# SH10_-_RS-485.net
KiCad netlist of a schematic drawn in Altium Designer
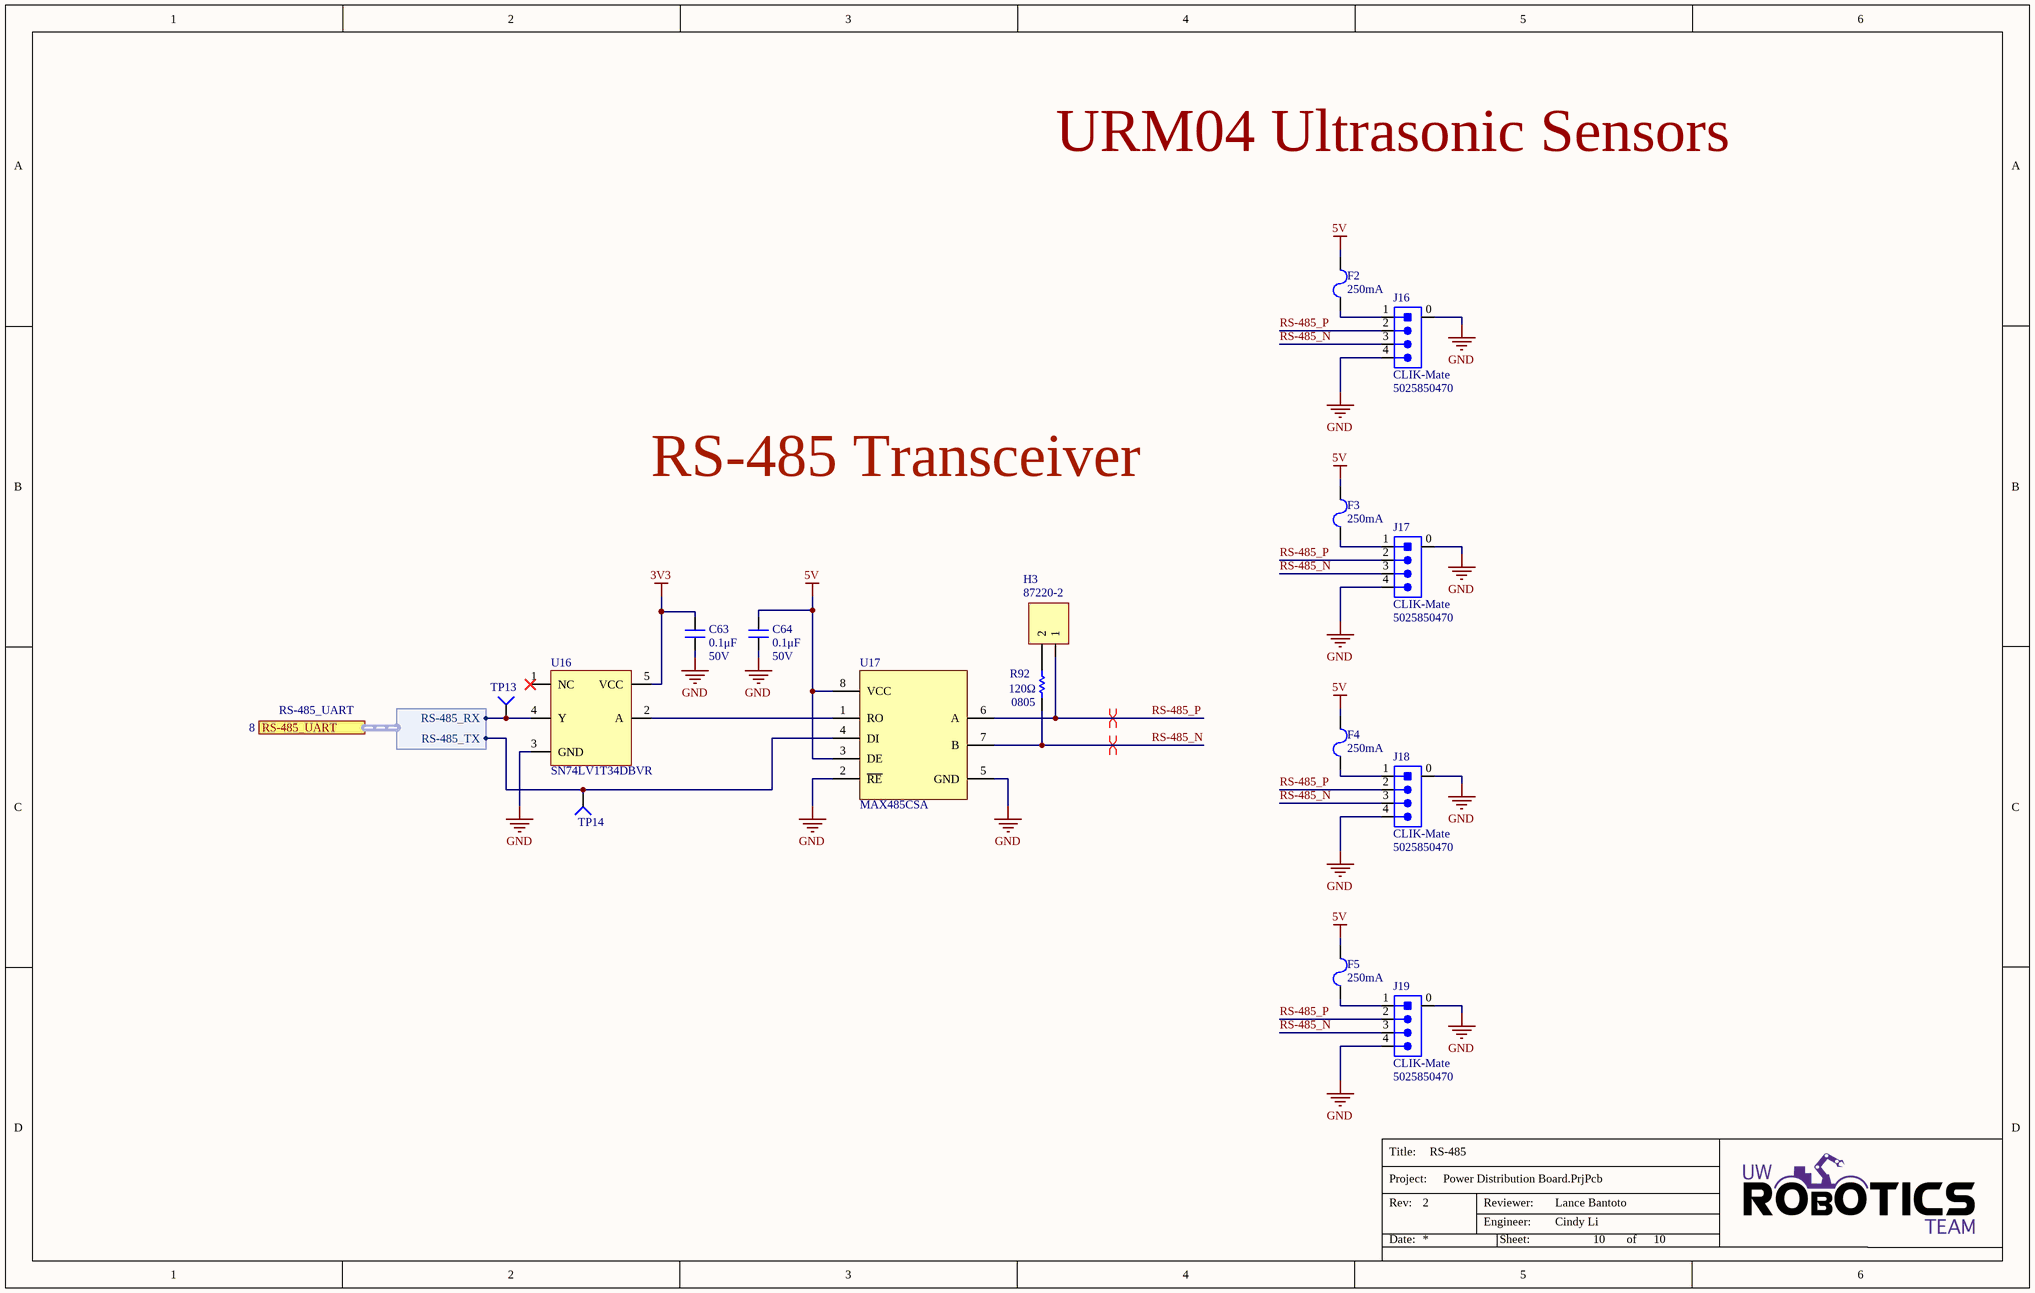
[diagram p0: SH10 - RS-485.SchDoc]

(export (version "E")
  (design (tool "Eeschema 10.0.6"))
  (components
    (comp (ref "C63")
      (value "0.1μF")
      (footprint "CAP2012")
      (description "CAP CER 0.1UF 50V X7R 0805")
      (fields
        (field (name "VOLTAGE RATING") "50V")
        (field (name "TOLERANCE") "10%")
        (field (name "LCSC PART #") "C49678")
      )
      (libsource (lib "UWRT_Schematic_Library_2020") (part "CAP_0.1uF_50V_0805"))
    )
    (comp (ref "C64")
      (value "0.1μF")
      (footprint "CAP2012")
      (description "CAP CER 0.1UF 50V X7R 0805")
      (fields
        (field (name "VOLTAGE RATING") "50V")
        (field (name "TOLERANCE") "10%")
        (field (name "LCSC PART #") "C49678")
      )
      (libsource (lib "UWRT_Schematic_Library_2020") (part "CAP_0.1uF_50V_0805"))
    )
    (comp (ref "F2")
      (value "FUSE_250mA_1206")
      (footprint "FUSE_1206")
      (description "FUSE BOARD MNT 250MA 125VAC/VDC")
      (fields (field (name "CURRENT RATING") "250mA"))
      (libsource (lib "UWRT_Schematic_Library_2020") (part "FUSE_250mA_1206"))
    )
    (comp (ref "F3")
      (value "FUSE_250mA_1206")
      (footprint "FUSE_1206")
      (description "FUSE BOARD MNT 250MA 125VAC/VDC")
      (fields (field (name "CURRENT RATING") "250mA"))
      (libsource (lib "UWRT_Schematic_Library_2020") (part "FUSE_250mA_1206"))
    )
    (comp (ref "F4")
      (value "FUSE_250mA_1206")
      (footprint "FUSE_1206")
      (description "FUSE BOARD MNT 250MA 125VAC/VDC")
      (fields (field (name "CURRENT RATING") "250mA"))
      (libsource (lib "UWRT_Schematic_Library_2020") (part "FUSE_250mA_1206"))
    )
    (comp (ref "F5")
      (value "FUSE_250mA_1206")
      (footprint "FUSE_1206")
      (description "FUSE BOARD MNT 250MA 125VAC/VDC")
      (fields (field (name "CURRENT RATING") "250mA"))
      (libsource (lib "UWRT_Schematic_Library_2020") (part "FUSE_250mA_1206"))
    )
    (comp (ref "H3")
      (value "JUMPER_2")
      (footprint "HDR1X2")
      (description "HEADER 2X1")
      (fields (field (name "MANUFACTURER PART NUMBER 1") "87220-2"))
      (libsource (lib "UWRT_Schematic_Library_2020") (part "JUMPER_2"))
    )
    (comp (ref "J16")
      (value "CON_4M_SM_RA")
      (footprint "MOLEX-5025850470")
      (description "CONN HEADER SMD RIGHT ANGLE 1.5 MM PITCH")
      (fields
        (field (name "MANUFACTURER") "Molex")
        (field (name "FAMILY") "CLIK-Mate")
        (field (name "MANUFACTOR NUMBER") "5025850470")
      )
      (libsource (lib "UWRT_Schematic_Library_2020") (part "CON_4M_SM_RA"))
    )
    (comp (ref "J17")
      (value "CON_4M_SM_RA")
      (footprint "MOLEX-5025850470")
      (description "CONN HEADER SMD RIGHT ANGLE 1.5 MM PITCH")
      (fields
        (field (name "MANUFACTURER") "Molex")
        (field (name "FAMILY") "CLIK-Mate")
        (field (name "MANUFACTOR NUMBER") "5025850470")
      )
      (libsource (lib "UWRT_Schematic_Library_2020") (part "CON_4M_SM_RA"))
    )
    (comp (ref "J18")
      (value "CON_4M_SM_RA")
      (footprint "MOLEX-5025850470")
      (description "CONN HEADER SMD RIGHT ANGLE 1.5 MM PITCH")
      (fields
        (field (name "MANUFACTURER") "Molex")
        (field (name "FAMILY") "CLIK-Mate")
        (field (name "MANUFACTOR NUMBER") "5025850470")
      )
      (libsource (lib "UWRT_Schematic_Library_2020") (part "CON_4M_SM_RA"))
    )
    (comp (ref "J19")
      (value "CON_4M_SM_RA")
      (footprint "MOLEX-5025850470")
      (description "CONN HEADER SMD RIGHT ANGLE 1.5 MM PITCH")
      (fields
        (field (name "MANUFACTURER") "Molex")
        (field (name "FAMILY") "CLIK-Mate")
        (field (name "MANUFACTOR NUMBER") "5025850470")
      )
      (libsource (lib "UWRT_Schematic_Library_2020") (part "CON_4M_SM_RA"))
    )
    (comp (ref "R92")
      (value "RES_120Ω_0805_1%")
      (footprint "RESC0805")
      (description "RES 120 OHM 1% 1/8W 0805")
      (fields
        (field (name "RESISTANCE") "120Ω")
        (field (name "LCSC PART #") "C17437")
        (field (name "PACKAGE/FOOTPRINT") "0805")
      )
      (libsource (lib "UWRT_Schematic_Library_2020") (part "RES_120Ω_0805_1%"))
    )
    (comp (ref "TP13")
      (value "TESTPOINT_1MM_CIRCLE")
      (footprint "TESTPOINT_CIRCLE_1MM")
      (description "TESTPOINT 1MM CIRCLE")
      (libsource (lib "UWRT_Schematic_Library_2020") (part "TESTPOINT_1MM_CIRCLE"))
    )
    (comp (ref "TP14")
      (value "TESTPOINT_1MM_CIRCLE")
      (footprint "TESTPOINT_CIRCLE_1MM")
      (description "TESTPOINT 1MM CIRCLE")
      (libsource (lib "UWRT_Schematic_Library_2020") (part "TESTPOINT_1MM_CIRCLE"))
    )
    (comp (ref "U16")
      (value "SN74LV1T34")
      (footprint "SN74LV1T34DBVR")
      (description "IC BUF NON-INVERT 5.5V SOT23-5")
      (fields
        (field (name "MANUFACTURER PART NUMBER 1") "SN74LV1T34DBVR")
        (field (name "LCSC PART #") "C100024")
      )
      (libsource (lib "UWRT_Schematic_Library_2020") (part "SN74LV1T34"))
    )
    (comp (ref "U17")
      (value "MAX485CSA")
      (footprint "SOIC127P600X175-8N")
      (description "IC TRANSCEIVER HALF 1/1 8SOIC RS422, RS485")
      (fields (field (name "LCSC PART #") "C9945"))
      (libsource (lib "UWRT_Schematic_Library_2020") (part "MAX485CSA"))
    )
  )
  (nets
    (net (code "2") (name "/RS-485_N") (class "Default")
      (node (ref "J16") (pin "3") (pinfunction "3_3") (pintype "passive"))
      (node (ref "J17") (pin "3") (pinfunction "3_3") (pintype "passive"))
      (node (ref "J18") (pin "3") (pinfunction "3_3") (pintype "passive"))
      (node (ref "J19") (pin "3") (pinfunction "3_3") (pintype "passive"))
      (node (ref "R92") (pin "1") (pinfunction "1_1") (pintype "passive"))
      (node (ref "U17") (pin "7") (pinfunction "B_7") (pintype "passive"))
    )
    (net (code "3") (name "/RS-485_P") (class "Default")
      (node (ref "H3") (pin "1") (pinfunction "1_1") (pintype "passive"))
      (node (ref "J16") (pin "2") (pinfunction "2_2") (pintype "passive"))
      (node (ref "J17") (pin "2") (pinfunction "2_2") (pintype "passive"))
      (node (ref "J18") (pin "2") (pinfunction "2_2") (pintype "passive"))
      (node (ref "J19") (pin "2") (pinfunction "2_2") (pintype "passive"))
      (node (ref "U17") (pin "6") (pinfunction "A_6") (pintype "passive"))
    )
    (net (code "5") (name "3V3") (class "Default")
      (node (ref "C63") (pin "1") (pinfunction "1_1") (pintype "passive"))
      (node (ref "U16") (pin "5") (pinfunction "VCC_5") (pintype "passive"))
    )
    (net (code "6") (name "5V") (class "Default")
      (node (ref "C64") (pin "1") (pinfunction "1_1") (pintype "passive"))
      (node (ref "F2") (pin "2") (pinfunction "2_2") (pintype "passive"))
      (node (ref "F3") (pin "2") (pinfunction "2_2") (pintype "passive"))
      (node (ref "F4") (pin "2") (pinfunction "2_2") (pintype "passive"))
      (node (ref "F5") (pin "2") (pinfunction "2_2") (pintype "passive"))
      (node (ref "U17") (pin "3") (pinfunction "DE_3") (pintype "passive"))
      (node (ref "U17") (pin "8") (pinfunction "VCC_8") (pintype "power_in"))
    )
    (net (code "7") (name "GND") (class "Default")
      (node (ref "C63") (pin "2") (pinfunction "2_2") (pintype "passive"))
      (node (ref "C64") (pin "2") (pinfunction "2_2") (pintype "passive"))
      (node (ref "J16") (pin "0") (pinfunction "0_0") (pintype "passive"))
      (node (ref "J16") (pin "4") (pinfunction "4_4") (pintype "passive"))
      (node (ref "J17") (pin "0") (pinfunction "0_0") (pintype "passive"))
      (node (ref "J17") (pin "4") (pinfunction "4_4") (pintype "passive"))
      (node (ref "J18") (pin "0") (pinfunction "0_0") (pintype "passive"))
      (node (ref "J18") (pin "4") (pinfunction "4_4") (pintype "passive"))
      (node (ref "J19") (pin "0") (pinfunction "0_0") (pintype "passive"))
      (node (ref "J19") (pin "4") (pinfunction "4_4") (pintype "passive"))
      (node (ref "U16") (pin "3") (pinfunction "GND_3") (pintype "passive"))
      (node (ref "U17") (pin "2") (pinfunction "~{RE}_2") (pintype "passive"))
      (node (ref "U17") (pin "5") (pinfunction "GND_5") (pintype "power_in"))
    )
    (net (code "8") (name "Net-(F2-Pad1)") (class "Default")
      (node (ref "F2") (pin "1") (pinfunction "1_1") (pintype "passive"))
      (node (ref "J16") (pin "1") (pinfunction "1_1") (pintype "passive"))
    )
    (net (code "9") (name "Net-(F3-Pad1)") (class "Default")
      (node (ref "F3") (pin "1") (pinfunction "1_1") (pintype "passive"))
      (node (ref "J17") (pin "1") (pinfunction "1_1") (pintype "passive"))
    )
    (net (code "10") (name "Net-(F4-Pad1)") (class "Default")
      (node (ref "F4") (pin "1") (pinfunction "1_1") (pintype "passive"))
      (node (ref "J18") (pin "1") (pinfunction "1_1") (pintype "passive"))
    )
    (net (code "11") (name "Net-(F5-Pad1)") (class "Default")
      (node (ref "F5") (pin "1") (pinfunction "1_1") (pintype "passive"))
      (node (ref "J19") (pin "1") (pinfunction "1_1") (pintype "passive"))
    )
    (net (code "12") (name "Net-(H3-Pad2)") (class "Default")
      (node (ref "H3") (pin "2") (pinfunction "2_2") (pintype "passive"))
      (node (ref "R92") (pin "2") (pinfunction "2_2") (pintype "passive"))
    )
    (net (code "13") (name "Net-(TP13-=value)") (class "Default")
      (node (ref "TP13") (pin "1") (pinfunction "=value_1") (pintype "passive"))
      (node (ref "U16") (pin "4") (pinfunction "Y_4") (pintype "passive"))
    )
    (net (code "14") (name "Net-(TP14-=value)") (class "Default")
      (node (ref "TP14") (pin "1") (pinfunction "=value_1") (pintype "passive"))
      (node (ref "U17") (pin "4") (pinfunction "DI_4") (pintype "passive"))
    )
    (net (code "15") (name "Net-(U16-A)") (class "Default")
      (node (ref "U16") (pin "2") (pinfunction "A_2") (pintype "passive"))
      (node (ref "U17") (pin "1") (pinfunction "RO_1") (pintype "passive"))
    )
    (net (code "16") (name "unconnected-(U16-NC-Pad1)") (class "Default")
      (node (ref "U16") (pin "1") (pinfunction "NC_1") (pintype "passive+no_connect"))
    )
  )
)
